# GroundComplete-6.net
KiCad netlist of a schematic drawn in EAGLE
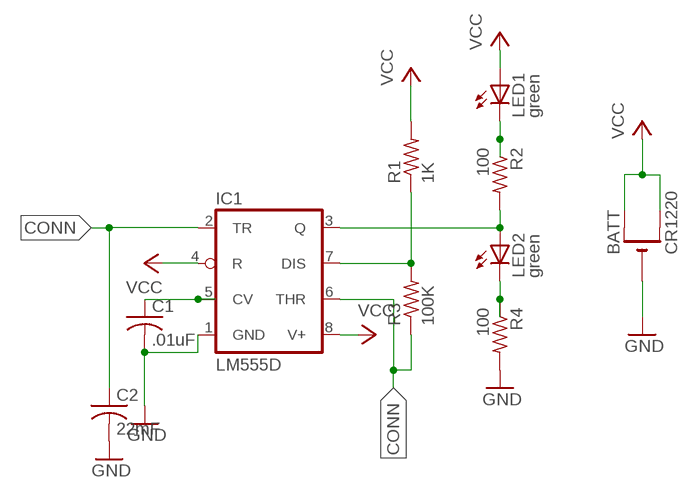
[diagram p0: schematic, sheet 1]

(export (version "E")
  (design (tool "Eeschema 10.0.6"))
  (components
    (comp (ref "BATT")
      (value "CR1220")
      (footprint "eagle-import:CR1220-SMD")
      (libsource (lib "eagle-import") (part "CR1220SMT"))
    )
    (comp (ref "C1")
      (value ".01uF")
      (footprint "eagle-import:C0805")
      (libsource (lib "eagle-import") (part "C-USC0805"))
    )
    (comp (ref "C2")
      (value "22mF")
      (footprint "eagle-import:C0805")
      (libsource (lib "eagle-import") (part "C-USC0805"))
    )
    (comp (ref "IC1")
      (value "LM555D")
      (footprint "eagle-import:SO08")
      (libsource (lib "eagle-import") (part "555DLM"))
    )
    (comp (ref "LED1")
      (value "green")
      (footprint "eagle-import:CHIPLED_0805")
      (libsource (lib "eagle-import") (part "LEDCHIPLED_0805"))
    )
    (comp (ref "LED2")
      (value "green")
      (footprint "eagle-import:CHIPLED_0805")
      (libsource (lib "eagle-import") (part "LEDCHIPLED_0805"))
    )
    (comp (ref "R1")
      (value "1K")
      (footprint "eagle-import:R0805")
      (libsource (lib "eagle-import") (part "R-US_R0805"))
    )
    (comp (ref "R2")
      (value "100")
      (footprint "eagle-import:R0805")
      (libsource (lib "eagle-import") (part "R-US_R0805"))
    )
    (comp (ref "R3")
      (value "100K")
      (footprint "eagle-import:R0805")
      (libsource (lib "eagle-import") (part "R-US_R0805"))
    )
    (comp (ref "R4")
      (value "100")
      (footprint "eagle-import:R0805")
      (libsource (lib "eagle-import") (part "R-US_R0805"))
    )
  )
  (nets
    (net (code "1") (name "CONN") (class "Default")
      (node (ref "C2") (pin "1") (pinfunction "1_1") (pintype "passive"))
      (node (ref "IC1") (pin "2") (pinfunction "TR_2") (pintype "input"))
      (node (ref "IC1") (pin "6") (pinfunction "THR_6") (pintype "input"))
      (node (ref "R3") (pin "1") (pinfunction "1_1") (pintype "passive"))
    )
    (net (code "2") (name "GND") (class "Default")
      (node (ref "BATT") (pin "-") (pinfunction "-_-") (pintype "passive"))
      (node (ref "C1") (pin "2") (pinfunction "2_2") (pintype "passive"))
      (node (ref "C2") (pin "2") (pinfunction "2_2") (pintype "passive"))
      (node (ref "IC1") (pin "1") (pinfunction "GND_1") (pintype "power_in"))
      (node (ref "R4") (pin "2") (pinfunction "2_2") (pintype "passive"))
    )
    (net (code "3") (name "Net-(IC1-CV)") (class "Default")
      (node (ref "C1") (pin "1") (pinfunction "1_1") (pintype "passive"))
      (node (ref "IC1") (pin "5") (pinfunction "CV_5") (pintype "input"))
    )
    (net (code "4") (name "Net-(IC1-DIS)") (class "Default")
      (node (ref "IC1") (pin "7") (pinfunction "DIS_7") (pintype "input"))
      (node (ref "R1") (pin "1") (pinfunction "1_1") (pintype "passive"))
      (node (ref "R3") (pin "2") (pinfunction "2_2") (pintype "passive"))
    )
    (net (code "5") (name "Net-(IC1-Q)") (class "Default")
      (node (ref "IC1") (pin "3") (pinfunction "Q_3") (pintype "output"))
      (node (ref "LED2") (pin "A") (pinfunction "A_A") (pintype "passive"))
      (node (ref "R2") (pin "2") (pinfunction "2_2") (pintype "passive"))
    )
    (net (code "6") (name "Net-(LED1-PadC)") (class "Default")
      (node (ref "LED1") (pin "C") (pinfunction "C_C") (pintype "passive"))
      (node (ref "R2") (pin "1") (pinfunction "1_1") (pintype "passive"))
    )
    (net (code "7") (name "Net-(LED2-PadC)") (class "Default")
      (node (ref "LED2") (pin "C") (pinfunction "C_C") (pintype "passive"))
      (node (ref "R4") (pin "1") (pinfunction "1_1") (pintype "passive"))
    )
    (net (code "8") (name "VCC") (class "Default")
      (node (ref "BATT") (pin "+$1") (pinfunction "+_+$1") (pintype "passive"))
      (node (ref "BATT") (pin "+$2") (pinfunction "+1_+$2") (pintype "passive"))
      (node (ref "IC1") (pin "4") (pinfunction "R_4") (pintype "input"))
      (node (ref "IC1") (pin "8") (pinfunction "V+_8") (pintype "power_in"))
      (node (ref "LED1") (pin "A") (pinfunction "A_A") (pintype "passive"))
      (node (ref "R1") (pin "2") (pinfunction "2_2") (pintype "passive"))
    )
  )
)
